# TBA820-Amplifier-2.net
KiCad netlist of a schematic drawn in EAGLE
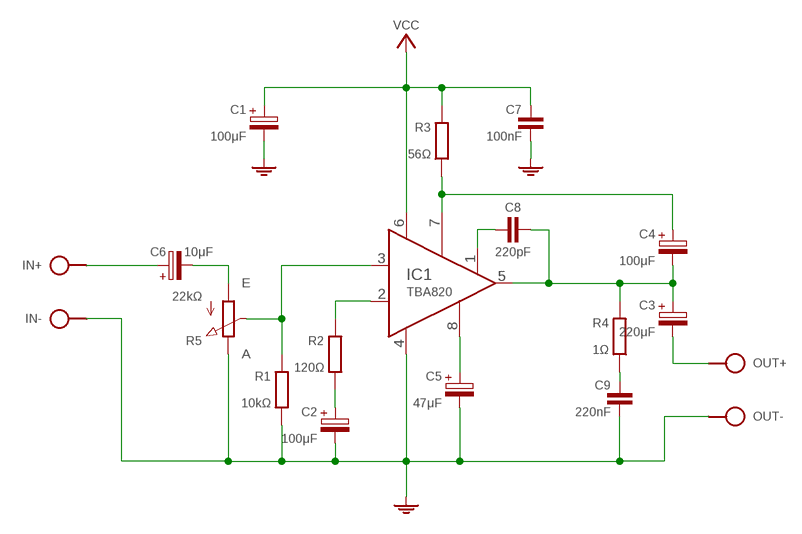
[diagram p0: schematic, sheet 1]

(export (version "E")
  (design (tool "Eeschema 10.0.6"))
  (components
    (comp (ref "C1")
      (value "100μF")
      (footprint "eagle-import:E2.5-4_V")
      (libsource (lib "eagle-import") (part "CPOLE2,5-4/V"))
    )
    (comp (ref "C2")
      (value "100μF")
      (footprint "eagle-import:E2.5-4_V")
      (libsource (lib "eagle-import") (part "CPOLE2,5-4/V"))
    )
    (comp (ref "C3")
      (value "220μF")
      (footprint "eagle-import:E2,5-5")
      (libsource (lib "eagle-import") (part "CPOLE2.5-5"))
    )
    (comp (ref "C4")
      (value "100μF")
      (footprint "eagle-import:E2.5-4_V")
      (libsource (lib "eagle-import") (part "CPOLE2,5-4/V"))
    )
    (comp (ref "C5")
      (value "47μF")
      (footprint "eagle-import:E2,5-3")
      (libsource (lib "eagle-import") (part "CPOLE2,5-3"))
    )
    (comp (ref "C6")
      (value "10μF")
      (footprint "eagle-import:E2,5-3")
      (libsource (lib "eagle-import") (part "CPOL-HE2,5-3"))
    )
    (comp (ref "C7")
      (value "100nF")
      (footprint "eagle-import:C025-024X044")
      (libsource (lib "eagle-import") (part "C025-024X044"))
    )
    (comp (ref "C8")
      (value "220pF")
      (footprint "eagle-import:C050-020X044")
      (libsource (lib "eagle-import") (part "C-H050-020X044"))
    )
    (comp (ref "C9")
      (value "220nF")
      (footprint "eagle-import:C050-024X044")
      (libsource (lib "eagle-import") (part "C050-024X044"))
    )
    (comp (ref "IC1")
      (value "TBA820")
      (footprint "eagle-import:DIL08")
      (libsource (lib "eagle-import") (part "TBA820"))
    )
    (comp (ref "IN")
      (value "SPAD+--+")
      (footprint "eagle-import:SPAD-+")
      (libsource (lib "eagle-import") (part "SPAD+--+"))
    )
    (comp (ref "OUT")
      (value "SPAD+-+-")
      (footprint "eagle-import:SPAD+-")
      (libsource (lib "eagle-import") (part "SPAD+-+-"))
    )
    (comp (ref "R1")
      (value "10kΩ")
      (footprint "eagle-import:0204_10-V")
      (libsource (lib "eagle-import") (part "R0204/10-V"))
    )
    (comp (ref "R2")
      (value "120Ω")
      (footprint "eagle-import:0202_2V")
      (libsource (lib "eagle-import") (part "R0202/2V"))
    )
    (comp (ref "R3")
      (value "56Ω")
      (footprint "eagle-import:0204_10-V")
      (libsource (lib "eagle-import") (part "R0204/10-V"))
    )
    (comp (ref "R4")
      (value "1Ω")
      (footprint "eagle-import:0204_10-V")
      (libsource (lib "eagle-import") (part "R0204/10-V"))
    )
    (comp (ref "R5")
      (value "22kΩ")
      (footprint "eagle-import:CONN-3P")
      (libsource (lib "eagle-import") (part "POT-3P"))
    )
    (comp (ref "S4")
      (value "VCC_GNDPWR-L")
      (footprint "eagle-import:PWR-L")
      (libsource (lib "eagle-import") (part "VCC_GNDPWR-L"))
    )
  )
  (nets
    (net (code "1") (name "GND") (class "Default")
      (node (ref "C1") (pin "-") (pinfunction "-_-") (pintype "passive"))
      (node (ref "C2") (pin "-") (pinfunction "-_-") (pintype "passive"))
      (node (ref "C5") (pin "-") (pinfunction "-_-") (pintype "passive"))
      (node (ref "C7") (pin "2") (pinfunction "2_2") (pintype "passive"))
      (node (ref "C9") (pin "2") (pinfunction "2_2") (pintype "passive"))
      (node (ref "IC1") (pin "4") (pinfunction "GND_4") (pintype "power_in"))
      (node (ref "IN") (pin "1") (pinfunction "P$1_1") (pintype "passive"))
      (node (ref "OUT") (pin "1") (pinfunction "P$1_1") (pintype "passive"))
      (node (ref "R1") (pin "2") (pinfunction "1_2") (pintype "passive"))
      (node (ref "R5") (pin "3") (pinfunction "E_3") (pintype "passive"))
      (node (ref "S4") (pin "1") (pinfunction "GND_1") (pintype "power_in"))
    )
    (net (code "2") (name "Net-(IC1-BOOT)") (class "Default")
      (node (ref "C4") (pin "+") (pinfunction "+_+") (pintype "passive"))
      (node (ref "IC1") (pin "7") (pinfunction "BOOT_7") (pintype "input"))
      (node (ref "R3") (pin "2") (pinfunction "1_2") (pintype "passive"))
    )
    (net (code "3") (name "Net-(IC1-FREQ)") (class "Default")
      (node (ref "C8") (pin "1") (pinfunction "1_1") (pintype "passive"))
      (node (ref "IC1") (pin "1") (pinfunction "FREQ_1") (pintype "input"))
    )
    (net (code "4") (name "Net-(IC1-GAIN)") (class "Default")
      (node (ref "IC1") (pin "2") (pinfunction "GAIN_2") (pintype "input"))
      (node (ref "R2") (pin "1") (pinfunction "2_1") (pintype "passive"))
    )
    (net (code "5") (name "Net-(IC1-INPUT)") (class "Default")
      (node (ref "IC1") (pin "3") (pinfunction "INPUT_3") (pintype "input"))
      (node (ref "R1") (pin "1") (pinfunction "2_1") (pintype "passive"))
      (node (ref "R5") (pin "2") (pinfunction "S_2") (pintype "passive"))
    )
    (net (code "6") (name "Net-(IC1-OUT)") (class "Default")
      (node (ref "C3") (pin "+") (pinfunction "+_+") (pintype "passive"))
      (node (ref "C4") (pin "-") (pinfunction "-_-") (pintype "passive"))
      (node (ref "C8") (pin "2") (pinfunction "2_2") (pintype "passive"))
      (node (ref "IC1") (pin "5") (pinfunction "OUT_5") (pintype "output"))
      (node (ref "R4") (pin "1") (pinfunction "2_1") (pintype "passive"))
    )
    (net (code "7") (name "Net-(IC1-RIPPLE)") (class "Default")
      (node (ref "C5") (pin "+") (pinfunction "+_+") (pintype "passive"))
      (node (ref "IC1") (pin "8") (pinfunction "RIPPLE_8") (pintype "input"))
    )
    (net (code "8") (name "Net-(IC1-VCC)") (class "Default")
      (node (ref "C1") (pin "+") (pinfunction "+_+") (pintype "passive"))
      (node (ref "C7") (pin "1") (pinfunction "1_1") (pintype "passive"))
      (node (ref "IC1") (pin "6") (pinfunction "VCC_6") (pintype "power_in"))
      (node (ref "R3") (pin "1") (pinfunction "2_1") (pintype "passive"))
      (node (ref "S4") (pin "2") (pinfunction "VCC_2") (pintype "power_in"))
    )
    (net (code "9") (name "Net-(INA-P$1)") (class "Default")
      (node (ref "C6") (pin "+") (pinfunction "+_+") (pintype "passive"))
      (node (ref "IN") (pin "2") (pinfunction "P$1_2") (pintype "passive"))
    )
    (net (code "10") (name "Net-(OUTA-P$1)") (class "Default")
      (node (ref "C3") (pin "-") (pinfunction "-_-") (pintype "passive"))
      (node (ref "OUT") (pin "2") (pinfunction "P$1_2") (pintype "passive"))
    )
    (net (code "11") (name "Net-(R2-1)") (class "Default")
      (node (ref "C2") (pin "+") (pinfunction "+_+") (pintype "passive"))
      (node (ref "R2") (pin "2") (pinfunction "1_2") (pintype "passive"))
    )
    (net (code "12") (name "Net-(R4-1)") (class "Default")
      (node (ref "C9") (pin "1") (pinfunction "1_1") (pintype "passive"))
      (node (ref "R4") (pin "2") (pinfunction "1_2") (pintype "passive"))
    )
    (net (code "13") (name "Net-(R5-A)") (class "Default")
      (node (ref "C6") (pin "-") (pinfunction "-_-") (pintype "passive"))
      (node (ref "R5") (pin "1") (pinfunction "A_1") (pintype "passive"))
    )
  )
)
